# TK520_GDT-Trafo.net
KiCad netlist of a schematic drawn in Altium Designer
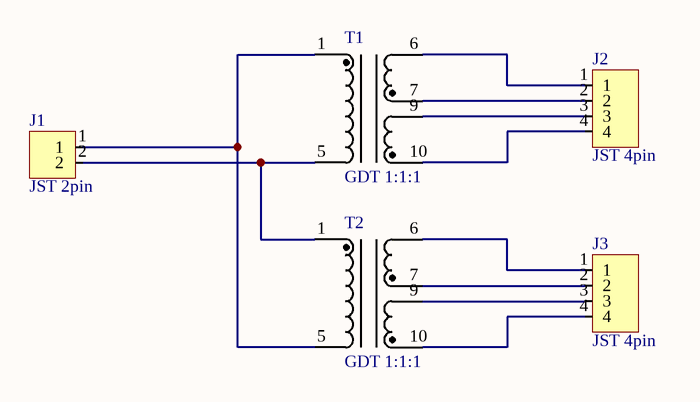
[diagram p0: TK520_GDT-Trafo.SchDoc]

(export (version "E")
  (design (tool "Eeschema 10.0.6"))
  (components
    (comp (ref "J1") (value "JST 2pin") (footprint "JST 2pin") (libsource (lib "Schlib1") (part "JST 2pin")))
    (comp (ref "J2") (value "JST 4pin") (footprint "JST 4pin") (libsource (lib "Schlib1") (part "JST 4pin")))
    (comp (ref "J3") (value "JST 4pin") (footprint "JST 4pin") (libsource (lib "Schlib1") (part "JST 4pin")))
    (comp (ref "T1")
      (value "GDT 1:1:1")
      (footprint "SD250-3")
      (libsource (lib "Schlib1") (part "GDT 1{colon}1{colon}1"))
    )
    (comp (ref "T2")
      (value "GDT 1:1:1")
      (footprint "SD250-3")
      (libsource (lib "Schlib1") (part "GDT 1{colon}1{colon}1"))
    )
  )
  (nets
    (net (code "1") (name "Net-(J1-Pad1)") (class "Default")
      (node (ref "J1") (pin "1") (pinfunction "1_1") (pintype "passive"))
      (node (ref "T1") (pin "1") (pinfunction "1_1") (pintype "passive"))
      (node (ref "T2") (pin "5") (pinfunction "5_5") (pintype "passive"))
    )
    (net (code "2") (name "Net-(J1-Pad2)") (class "Default")
      (node (ref "J1") (pin "2") (pinfunction "2_2") (pintype "passive"))
      (node (ref "T1") (pin "5") (pinfunction "5_5") (pintype "passive"))
      (node (ref "T2") (pin "1") (pinfunction "1_1") (pintype "passive"))
    )
    (net (code "3") (name "Net-(J2-Pad1)") (class "Default")
      (node (ref "J2") (pin "1") (pinfunction "1_1") (pintype "passive"))
      (node (ref "T1") (pin "6") (pinfunction "6_6") (pintype "passive"))
    )
    (net (code "4") (name "Net-(J2-Pad2)") (class "Default")
      (node (ref "J2") (pin "2") (pinfunction "2_2") (pintype "passive"))
      (node (ref "T1") (pin "7") (pinfunction "7_7") (pintype "passive"))
    )
    (net (code "5") (name "Net-(J2-Pad3)") (class "Default")
      (node (ref "J2") (pin "3") (pinfunction "3_3") (pintype "passive"))
      (node (ref "T1") (pin "9") (pinfunction "9_9") (pintype "passive"))
    )
    (net (code "6") (name "Net-(J2-Pad4)") (class "Default")
      (node (ref "J2") (pin "4") (pinfunction "4_4") (pintype "passive"))
      (node (ref "T1") (pin "10") (pinfunction "10_10") (pintype "passive"))
    )
    (net (code "7") (name "Net-(J3-Pad1)") (class "Default")
      (node (ref "J3") (pin "1") (pinfunction "1_1") (pintype "passive"))
      (node (ref "T2") (pin "6") (pinfunction "6_6") (pintype "passive"))
    )
    (net (code "8") (name "Net-(J3-Pad2)") (class "Default")
      (node (ref "J3") (pin "2") (pinfunction "2_2") (pintype "passive"))
      (node (ref "T2") (pin "7") (pinfunction "7_7") (pintype "passive"))
    )
    (net (code "9") (name "Net-(J3-Pad3)") (class "Default")
      (node (ref "J3") (pin "3") (pinfunction "3_3") (pintype "passive"))
      (node (ref "T2") (pin "9") (pinfunction "9_9") (pintype "passive"))
    )
    (net (code "10") (name "Net-(J3-Pad4)") (class "Default")
      (node (ref "J3") (pin "4") (pinfunction "4_4") (pintype "passive"))
      (node (ref "T2") (pin "10") (pinfunction "10_10") (pintype "passive"))
    )
  )
)
